# ripples_v40.net
KiCad netlist of a schematic drawn in EAGLE
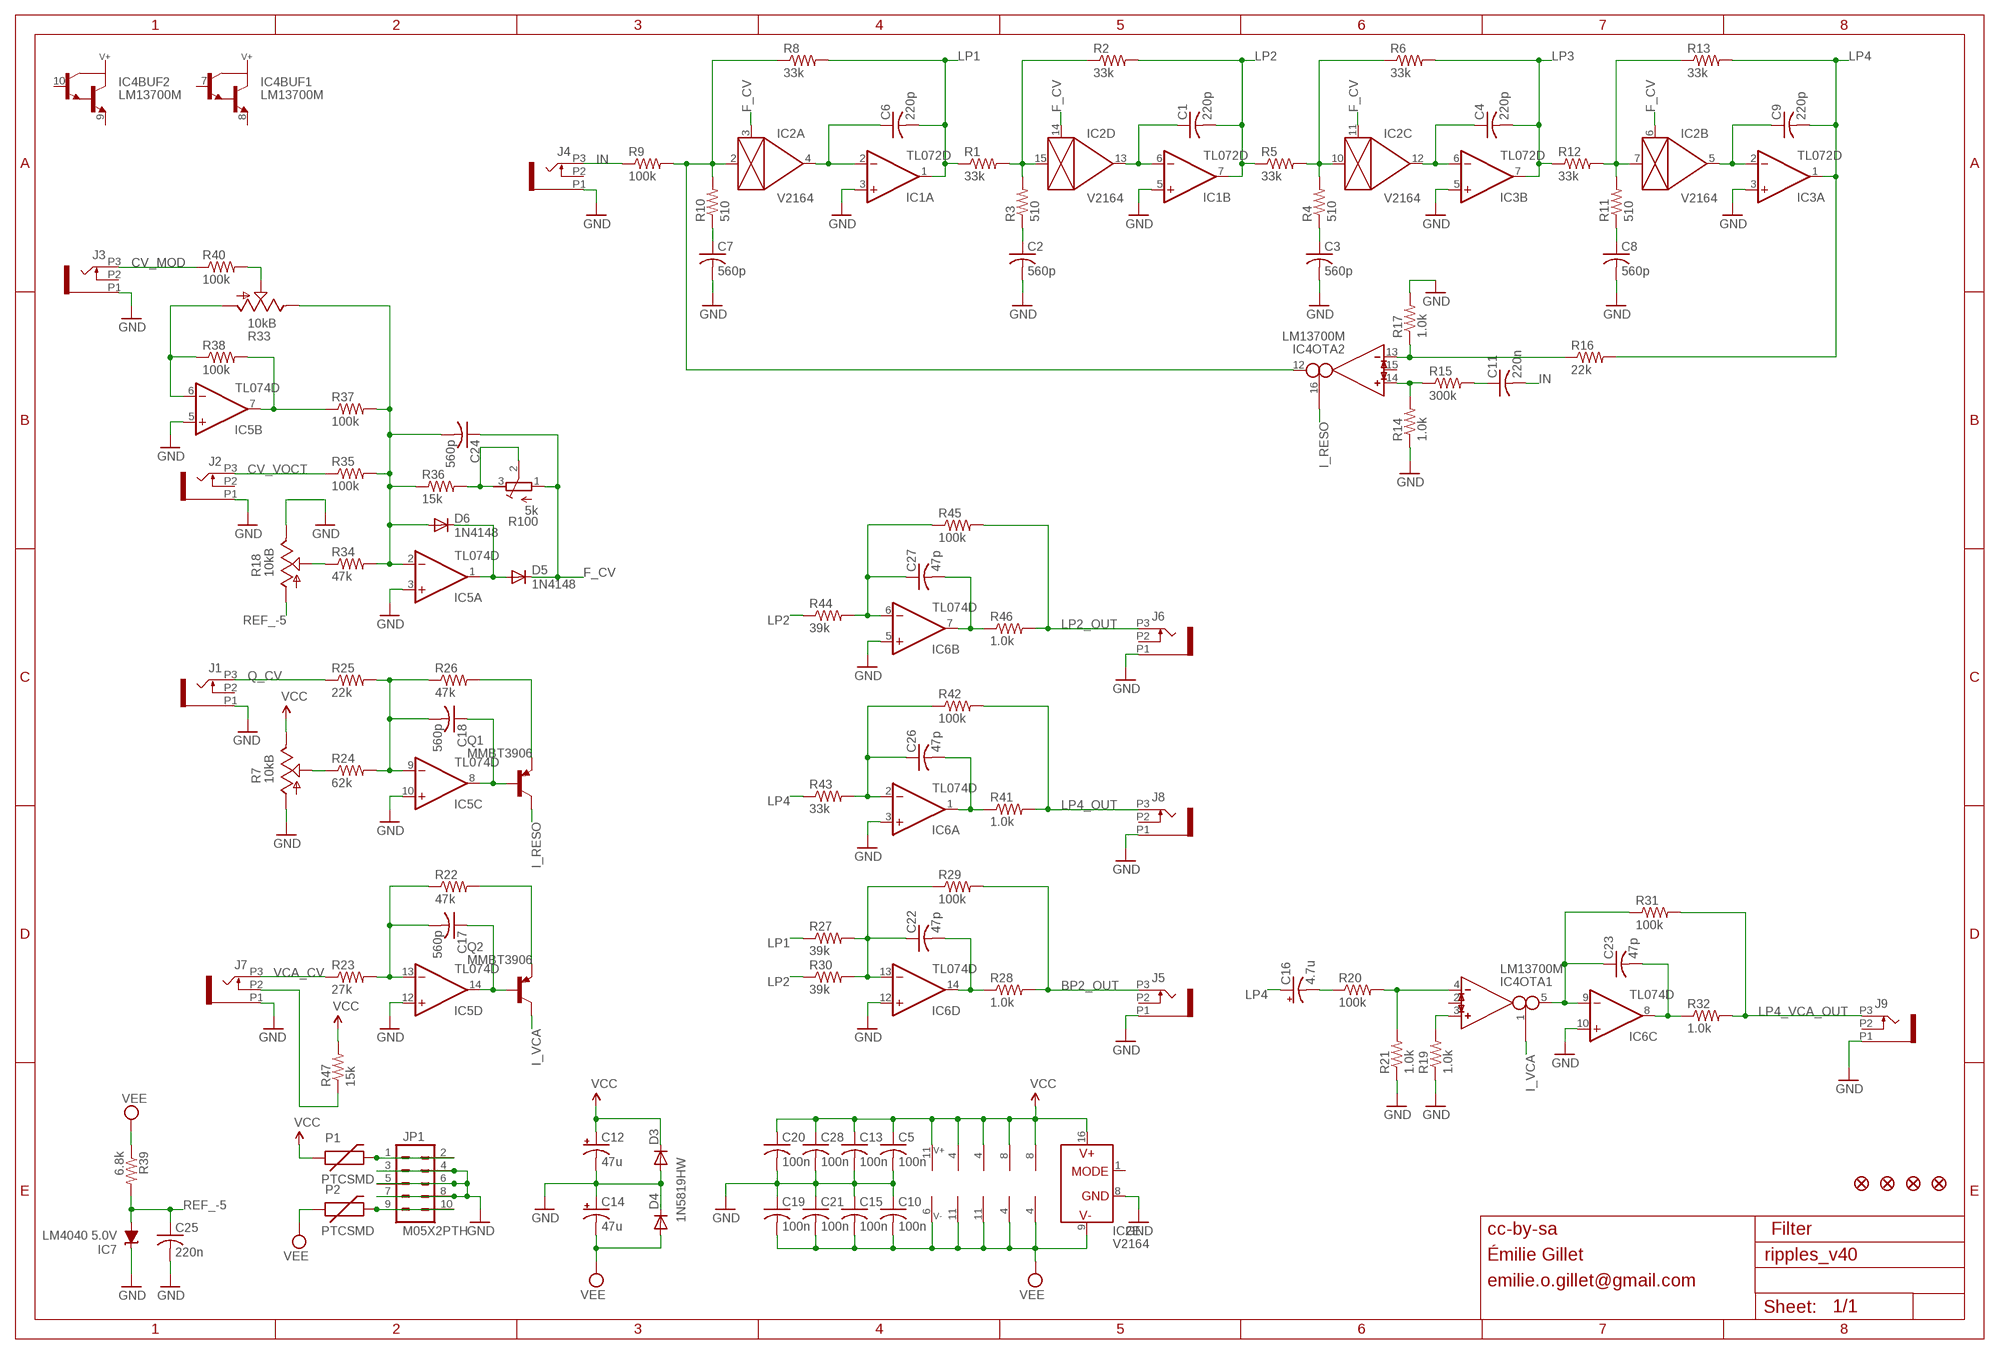
[diagram p0: schematic, sheet 1]

(export (version "E")
  (design (tool "Eeschema 10.0.6"))
  (components
    (comp (ref "C1")
      (value "220p")
      (footprint "eagle-import:C0603")
      (libsource (lib "eagle-import") (part "C-USC0603"))
    )
    (comp (ref "C2")
      (value "560p")
      (footprint "eagle-import:C0603")
      (libsource (lib "eagle-import") (part "C-USC0603"))
    )
    (comp (ref "C3")
      (value "560p")
      (footprint "eagle-import:C0603")
      (libsource (lib "eagle-import") (part "C-USC0603"))
    )
    (comp (ref "C4")
      (value "220p")
      (footprint "eagle-import:C0603")
      (libsource (lib "eagle-import") (part "C-USC0603"))
    )
    (comp (ref "C5")
      (value "100n")
      (footprint "eagle-import:C0603")
      (libsource (lib "eagle-import") (part "C-USC0603"))
    )
    (comp (ref "C6")
      (value "220p")
      (footprint "eagle-import:C0603")
      (libsource (lib "eagle-import") (part "C-USC0603"))
    )
    (comp (ref "C7")
      (value "560p")
      (footprint "eagle-import:C0603")
      (libsource (lib "eagle-import") (part "C-USC0603"))
    )
    (comp (ref "C8")
      (value "560p")
      (footprint "eagle-import:C0603")
      (libsource (lib "eagle-import") (part "C-USC0603"))
    )
    (comp (ref "C9")
      (value "220p")
      (footprint "eagle-import:C0603")
      (libsource (lib "eagle-import") (part "C-USC0603"))
    )
    (comp (ref "C10")
      (value "100n")
      (footprint "eagle-import:C0603")
      (libsource (lib "eagle-import") (part "C-USC0603"))
    )
    (comp (ref "C11")
      (value "220n")
      (footprint "eagle-import:C0603")
      (libsource (lib "eagle-import") (part "C-USC0603"))
    )
    (comp (ref "C12")
      (value "47u")
      (footprint "eagle-import:PANASONIC_D")
      (libsource (lib "eagle-import") (part "CPOL-USD"))
    )
    (comp (ref "C13")
      (value "100n")
      (footprint "eagle-import:C0603")
      (libsource (lib "eagle-import") (part "C-USC0603"))
    )
    (comp (ref "C14")
      (value "47u")
      (footprint "eagle-import:PANASONIC_D")
      (libsource (lib "eagle-import") (part "CPOL-USD"))
    )
    (comp (ref "C15")
      (value "100n")
      (footprint "eagle-import:C0603")
      (libsource (lib "eagle-import") (part "C-USC0603"))
    )
    (comp (ref "C16")
      (value "4.7u")
      (footprint "eagle-import:PANASONIC_B")
      (libsource (lib "eagle-import") (part "CPOL-USB"))
    )
    (comp (ref "C17")
      (value "560p")
      (footprint "eagle-import:C0603")
      (libsource (lib "eagle-import") (part "C-USC0603"))
    )
    (comp (ref "C18")
      (value "560p")
      (footprint "eagle-import:C0603")
      (libsource (lib "eagle-import") (part "C-USC0603"))
    )
    (comp (ref "C19")
      (value "100n")
      (footprint "eagle-import:C0603")
      (libsource (lib "eagle-import") (part "C-USC0603"))
    )
    (comp (ref "C20")
      (value "100n")
      (footprint "eagle-import:C0603")
      (libsource (lib "eagle-import") (part "C-USC0603"))
    )
    (comp (ref "C21")
      (value "100n")
      (footprint "eagle-import:C0603")
      (libsource (lib "eagle-import") (part "C-USC0603"))
    )
    (comp (ref "C22")
      (value "47p")
      (footprint "eagle-import:C0603")
      (libsource (lib "eagle-import") (part "C-USC0603"))
    )
    (comp (ref "C23")
      (value "47p")
      (footprint "eagle-import:C0603")
      (libsource (lib "eagle-import") (part "C-USC0603"))
    )
    (comp (ref "C24")
      (value "560p")
      (footprint "eagle-import:C0603")
      (libsource (lib "eagle-import") (part "C-USC0603"))
    )
    (comp (ref "C25")
      (value "220n")
      (footprint "eagle-import:C0603")
      (libsource (lib "eagle-import") (part "C-USC0603"))
    )
    (comp (ref "C26")
      (value "47p")
      (footprint "eagle-import:C0603")
      (libsource (lib "eagle-import") (part "C-USC0603"))
    )
    (comp (ref "C27")
      (value "47p")
      (footprint "eagle-import:C0603")
      (libsource (lib "eagle-import") (part "C-USC0603"))
    )
    (comp (ref "C28")
      (value "100n")
      (footprint "eagle-import:C0603")
      (libsource (lib "eagle-import") (part "C-USC0603"))
    )
    (comp (ref "D3")
      (value "1N5819HW")
      (footprint "eagle-import:SOD123")
      (libsource (lib "eagle-import") (part "DIODE-SOD123"))
    )
    (comp (ref "D4")
      (value "1N5819HW")
      (footprint "eagle-import:SOD123")
      (libsource (lib "eagle-import") (part "DIODE-SOD123"))
    )
    (comp (ref "D5")
      (value "1N4148")
      (footprint "eagle-import:SOD323-W")
      (libsource (lib "eagle-import") (part "DIODE-SOD323-W"))
    )
    (comp (ref "D6")
      (value "1N4148")
      (footprint "eagle-import:SOD323-W")
      (libsource (lib "eagle-import") (part "DIODE-SOD323-W"))
    )
    (comp (ref "F1")
      (value "FIDUCIAL1X2")
      (footprint "eagle-import:FIDUCIAL-1X2")
      (libsource (lib "eagle-import") (part "FIDUCIAL1X2"))
    )
    (comp (ref "F2")
      (value "FIDUCIAL1X2")
      (footprint "eagle-import:FIDUCIAL-1X2")
      (libsource (lib "eagle-import") (part "FIDUCIAL1X2"))
    )
    (comp (ref "F3")
      (value "FIDUCIAL1X2")
      (footprint "eagle-import:FIDUCIAL-1X2")
      (libsource (lib "eagle-import") (part "FIDUCIAL1X2"))
    )
    (comp (ref "F4")
      (value "FIDUCIAL1X2")
      (footprint "eagle-import:FIDUCIAL-1X2")
      (libsource (lib "eagle-import") (part "FIDUCIAL1X2"))
    )
    (comp (ref "IC1")
      (value "TL072D")
      (footprint "eagle-import:SO08")
      (libsource (lib "eagle-import") (part "TL072D"))
    )
    (comp (ref "IC2")
      (value "V2164")
      (footprint "eagle-import:SOIC16N")
      (libsource (lib "eagle-import") (part "SSM2164S"))
    )
    (comp (ref "IC3")
      (value "TL072D")
      (footprint "eagle-import:SO08")
      (libsource (lib "eagle-import") (part "TL072D"))
    )
    (comp (ref "IC4")
      (value "LM13700M")
      (footprint "eagle-import:SO16")
      (libsource (lib "eagle-import") (part "LM13700M"))
    )
    (comp (ref "IC5")
      (value "TL074D")
      (footprint "eagle-import:SO14")
      (libsource (lib "eagle-import") (part "TL074D"))
    )
    (comp (ref "IC6")
      (value "TL074D")
      (footprint "eagle-import:SO14")
      (libsource (lib "eagle-import") (part "TL074D"))
    )
    (comp (ref "IC7")
      (value "LM4040 5.0V")
      (footprint "eagle-import:DBZ_R-PDSO-G3")
      (libsource (lib "eagle-import") (part "LM4041DBZC12"))
    )
    (comp (ref "J1")
      (value "PJ301_THONKICONN6")
      (footprint "eagle-import:WQP_PJ_301M6")
      (libsource (lib "eagle-import") (part "PJ301_THONKICONN6"))
    )
    (comp (ref "J2")
      (value "PJ301_THONKICONN6")
      (footprint "eagle-import:WQP_PJ_301M6")
      (libsource (lib "eagle-import") (part "PJ301_THONKICONN6"))
    )
    (comp (ref "J3")
      (value "PJ301_THONKICONN6")
      (footprint "eagle-import:WQP_PJ_301M6")
      (libsource (lib "eagle-import") (part "PJ301_THONKICONN6"))
    )
    (comp (ref "J4")
      (value "PJ301_THONKICONN6")
      (footprint "eagle-import:WQP_PJ_301M6")
      (libsource (lib "eagle-import") (part "PJ301_THONKICONN6"))
    )
    (comp (ref "J5")
      (value "PJ301_THONKICONN6")
      (footprint "eagle-import:WQP_PJ_301M6")
      (libsource (lib "eagle-import") (part "PJ301_THONKICONN6"))
    )
    (comp (ref "J6")
      (value "PJ301_THONKICONN6")
      (footprint "eagle-import:WQP_PJ_301M6")
      (libsource (lib "eagle-import") (part "PJ301_THONKICONN6"))
    )
    (comp (ref "J7")
      (value "PJ301_THONKICONN6")
      (footprint "eagle-import:WQP_PJ_301M6")
      (libsource (lib "eagle-import") (part "PJ301_THONKICONN6"))
    )
    (comp (ref "J8")
      (value "PJ301_THONKICONN6")
      (footprint "eagle-import:WQP_PJ_301M6")
      (libsource (lib "eagle-import") (part "PJ301_THONKICONN6"))
    )
    (comp (ref "J9")
      (value "PJ301_THONKICONN6")
      (footprint "eagle-import:WQP_PJ_301M6")
      (libsource (lib "eagle-import") (part "PJ301_THONKICONN6"))
    )
    (comp (ref "JP1")
      (value "M05X2PTH")
      (footprint "eagle-import:AVR_ICSP")
      (libsource (lib "eagle-import") (part "M05X2PTH"))
    )
    (comp (ref "P1")
      (value "PTCSMD")
      (footprint "eagle-import:PTC-1206")
      (libsource (lib "eagle-import") (part "PTCSMD"))
    )
    (comp (ref "P2")
      (value "PTCSMD")
      (footprint "eagle-import:PTC-1206")
      (libsource (lib "eagle-import") (part "PTCSMD"))
    )
    (comp (ref "Q1")
      (value "MMBT3906")
      (footprint "eagle-import:SOT23-BEC")
      (libsource (lib "eagle-import") (part "-PNP-SOT23-BECMMBT3906LT1"))
    )
    (comp (ref "Q2")
      (value "MMBT3906")
      (footprint "eagle-import:SOT23-BEC")
      (libsource (lib "eagle-import") (part "-PNP-SOT23-BECMMBT3906LT1"))
    )
    (comp (ref "R1")
      (value "33k")
      (footprint "eagle-import:R0603")
      (libsource (lib "eagle-import") (part "R-US_R0603"))
    )
    (comp (ref "R2")
      (value "33k")
      (footprint "eagle-import:R0603")
      (libsource (lib "eagle-import") (part "R-US_R0603"))
    )
    (comp (ref "R3")
      (value "510")
      (footprint "eagle-import:R0603")
      (libsource (lib "eagle-import") (part "R-US_R0603"))
    )
    (comp (ref "R4")
      (value "510")
      (footprint "eagle-import:R0603")
      (libsource (lib "eagle-import") (part "R-US_R0603"))
    )
    (comp (ref "R5")
      (value "33k")
      (footprint "eagle-import:R0603")
      (libsource (lib "eagle-import") (part "R-US_R0603"))
    )
    (comp (ref "R6")
      (value "33k")
      (footprint "eagle-import:R0603")
      (libsource (lib "eagle-import") (part "R-US_R0603"))
    )
    (comp (ref "R7")
      (value "10kB")
      (footprint "eagle-import:ALPS_POT_VERTICAL_PS")
      (libsource (lib "eagle-import") (part "POT_USVERTICAL_PS"))
    )
    (comp (ref "R8")
      (value "33k")
      (footprint "eagle-import:R0603")
      (libsource (lib "eagle-import") (part "R-US_R0603"))
    )
    (comp (ref "R9")
      (value "100k")
      (footprint "eagle-import:R0603")
      (libsource (lib "eagle-import") (part "R-US_R0603"))
    )
    (comp (ref "R10")
      (value "510")
      (footprint "eagle-import:R0603")
      (libsource (lib "eagle-import") (part "R-US_R0603"))
    )
    (comp (ref "R11")
      (value "510")
      (footprint "eagle-import:R0603")
      (libsource (lib "eagle-import") (part "R-US_R0603"))
    )
    (comp (ref "R12")
      (value "33k")
      (footprint "eagle-import:R0603")
      (libsource (lib "eagle-import") (part "R-US_R0603"))
    )
    (comp (ref "R13")
      (value "33k")
      (footprint "eagle-import:R0603")
      (libsource (lib "eagle-import") (part "R-US_R0603"))
    )
    (comp (ref "R14")
      (value "1.0k")
      (footprint "eagle-import:R0603")
      (libsource (lib "eagle-import") (part "R-US_R0603"))
    )
    (comp (ref "R15")
      (value "300k")
      (footprint "eagle-import:R0603")
      (libsource (lib "eagle-import") (part "R-US_R0603"))
    )
    (comp (ref "R16")
      (value "22k")
      (footprint "eagle-import:R0603")
      (libsource (lib "eagle-import") (part "R-US_R0603"))
    )
    (comp (ref "R17")
      (value "1.0k")
      (footprint "eagle-import:R0603")
      (libsource (lib "eagle-import") (part "R-US_R0603"))
    )
    (comp (ref "R18")
      (value "10kB")
      (footprint "eagle-import:ALPS_POT_VERTICAL_PS")
      (libsource (lib "eagle-import") (part "POT_USVERTICAL_PS"))
    )
    (comp (ref "R19")
      (value "1.0k")
      (footprint "eagle-import:R0603")
      (libsource (lib "eagle-import") (part "R-US_R0603"))
    )
    (comp (ref "R20")
      (value "100k")
      (footprint "eagle-import:R0603")
      (libsource (lib "eagle-import") (part "R-US_R0603"))
    )
    (comp (ref "R21")
      (value "1.0k")
      (footprint "eagle-import:R0603")
      (libsource (lib "eagle-import") (part "R-US_R0603"))
    )
    (comp (ref "R22")
      (value "47k")
      (footprint "eagle-import:R0603")
      (libsource (lib "eagle-import") (part "R-US_R0603"))
    )
    (comp (ref "R23")
      (value "27k")
      (footprint "eagle-import:R0603")
      (libsource (lib "eagle-import") (part "R-US_R0603"))
    )
    (comp (ref "R24")
      (value "62k")
      (footprint "eagle-import:R0603")
      (libsource (lib "eagle-import") (part "R-US_R0603"))
    )
    (comp (ref "R25")
      (value "22k")
      (footprint "eagle-import:R0603")
      (libsource (lib "eagle-import") (part "R-US_R0603"))
    )
    (comp (ref "R26")
      (value "47k")
      (footprint "eagle-import:R0603")
      (libsource (lib "eagle-import") (part "R-US_R0603"))
    )
    (comp (ref "R27")
      (value "39k")
      (footprint "eagle-import:R0603")
      (libsource (lib "eagle-import") (part "R-US_R0603"))
    )
    (comp (ref "R28")
      (value "1.0k")
      (footprint "eagle-import:R0603")
      (libsource (lib "eagle-import") (part "R-US_R0603"))
    )
    (comp (ref "R29")
      (value "100k")
      (footprint "eagle-import:R0603")
      (libsource (lib "eagle-import") (part "R-US_R0603"))
    )
    (comp (ref "R30")
      (value "39k")
      (footprint "eagle-import:R0603")
      (libsource (lib "eagle-import") (part "R-US_R0603"))
    )
    (comp (ref "R31")
      (value "100k")
      (footprint "eagle-import:R0603")
      (libsource (lib "eagle-import") (part "R-US_R0603"))
    )
    (comp (ref "R32")
      (value "1.0k")
      (footprint "eagle-import:R0603")
      (libsource (lib "eagle-import") (part "R-US_R0603"))
    )
    (comp (ref "R33")
      (value "10kB")
      (footprint "eagle-import:ALPS_POT_VERTICAL_PS")
      (libsource (lib "eagle-import") (part "POT_USVERTICAL_PS"))
    )
    (comp (ref "R34")
      (value "47k")
      (footprint "eagle-import:R0603")
      (libsource (lib "eagle-import") (part "R-US_R0603"))
    )
    (comp (ref "R35")
      (value "100k")
      (footprint "eagle-import:R0603")
      (libsource (lib "eagle-import") (part "R-US_R0603"))
    )
    (comp (ref "R36")
      (value "15k")
      (footprint "eagle-import:R0603")
      (libsource (lib "eagle-import") (part "R-US_R0603"))
    )
    (comp (ref "R37")
      (value "100k")
      (footprint "eagle-import:R0603")
      (libsource (lib "eagle-import") (part "R-US_R0603"))
    )
    (comp (ref "R38")
      (value "100k")
      (footprint "eagle-import:R0603")
      (libsource (lib "eagle-import") (part "R-US_R0603"))
    )
    (comp (ref "R39")
      (value "6.8k")
      (footprint "eagle-import:R0603")
      (libsource (lib "eagle-import") (part "resistor_R-US_R0603"))
    )
    (comp (ref "R40")
      (value "100k")
      (footprint "eagle-import:R0603")
      (libsource (lib "eagle-import") (part "R-US_R0603"))
    )
    (comp (ref "R41")
      (value "1.0k")
      (footprint "eagle-import:R0603")
      (libsource (lib "eagle-import") (part "R-US_R0603"))
    )
    (comp (ref "R42")
      (value "100k")
      (footprint "eagle-import:R0603")
      (libsource (lib "eagle-import") (part "R-US_R0603"))
    )
    (comp (ref "R43")
      (value "33k")
      (footprint "eagle-import:R0603")
      (libsource (lib "eagle-import") (part "R-US_R0603"))
    )
    (comp (ref "R44")
      (value "39k")
      (footprint "eagle-import:R0603")
      (libsource (lib "eagle-import") (part "R-US_R0603"))
    )
    (comp (ref "R45")
      (value "100k")
      (footprint "eagle-import:R0603")
      (libsource (lib "eagle-import") (part "R-US_R0603"))
    )
    (comp (ref "R46")
      (value "1.0k")
      (footprint "eagle-import:R0603")
      (libsource (lib "eagle-import") (part "R-US_R0603"))
    )
    (comp (ref "R47")
      (value "15k")
      (footprint "eagle-import:R0603")
      (libsource (lib "eagle-import") (part "R-US_R0603"))
    )
    (comp (ref "R100")
      (value "5k")
      (footprint "eagle-import:RTRIM3296X")
      (libsource (lib "eagle-import") (part "R-TRIMM3296X"))
    )
  )
  (nets
    (net (code "1") (name "/BP2_OUT") (class "Default")
      (node (ref "J5") (pin "P3") (pinfunction "3_P3") (pintype "passive"))
      (node (ref "R28") (pin "2") (pinfunction "2_2") (pintype "passive"))
      (node (ref "R29") (pin "2") (pinfunction "2_2") (pintype "passive"))
    )
    (net (code "2") (name "/CV_MOD") (class "Default")
      (node (ref "J3") (pin "P3") (pinfunction "3_P3") (pintype "passive"))
      (node (ref "R40") (pin "1") (pinfunction "1_1") (pintype "passive"))
    )
    (net (code "3") (name "/CV_VOCT") (class "Default")
      (node (ref "J2") (pin "P3") (pinfunction "3_P3") (pintype "passive"))
      (node (ref "R35") (pin "1") (pinfunction "1_1") (pintype "passive"))
    )
    (net (code "4") (name "/F_CV") (class "Default")
      (node (ref "C24") (pin "1") (pinfunction "1_1") (pintype "passive"))
      (node (ref "D5") (pin "C") (pinfunction "C_C") (pintype "passive"))
      (node (ref "IC2") (pin "11") (pinfunction "CTRL_11") (pintype "input"))
      (node (ref "IC2") (pin "14") (pinfunction "CTRL_14") (pintype "input"))
      (node (ref "IC2") (pin "3") (pinfunction "CTRL_3") (pintype "input"))
      (node (ref "IC2") (pin "6") (pinfunction "CTRL_6") (pintype "input"))
      (node (ref "R100") (pin "1") (pinfunction "E_1") (pintype "passive"))
    )
    (net (code "5") (name "/IN") (class "Default")
      (node (ref "C11") (pin "2") (pinfunction "2_2") (pintype "passive"))
      (node (ref "J4") (pin "P3") (pinfunction "3_P3") (pintype "passive"))
      (node (ref "R9") (pin "1") (pinfunction "1_1") (pintype "passive"))
    )
    (net (code "6") (name "/I_RESO") (class "Default")
      (node (ref "IC4") (pin "16") (pinfunction "I_BIAS_16") (pintype "input"))
      (node (ref "Q1") (pin "C") (pinfunction "C_C") (pintype "passive"))
    )
    (net (code "7") (name "/I_VCA") (class "Default")
      (node (ref "IC4") (pin "1") (pinfunction "I_BIAS_1") (pintype "input"))
      (node (ref "Q2") (pin "C") (pinfunction "C_C") (pintype "passive"))
    )
    (net (code "8") (name "/LP1") (class "Default")
      (node (ref "C6") (pin "2") (pinfunction "2_2") (pintype "passive"))
      (node (ref "IC1") (pin "1") (pinfunction "OUT_1") (pintype "output"))
      (node (ref "R1") (pin "1") (pinfunction "1_1") (pintype "passive"))
      (node (ref "R27") (pin "1") (pinfunction "1_1") (pintype "passive"))
      (node (ref "R8") (pin "2") (pinfunction "2_2") (pintype "passive"))
    )
    (net (code "9") (name "/LP2") (class "Default")
      (node (ref "C1") (pin "2") (pinfunction "2_2") (pintype "passive"))
      (node (ref "IC1") (pin "7") (pinfunction "OUT_7") (pintype "output"))
      (node (ref "R2") (pin "2") (pinfunction "2_2") (pintype "passive"))
      (node (ref "R30") (pin "1") (pinfunction "1_1") (pintype "passive"))
      (node (ref "R44") (pin "1") (pinfunction "1_1") (pintype "passive"))
      (node (ref "R5") (pin "1") (pinfunction "1_1") (pintype "passive"))
    )
    (net (code "10") (name "/LP2_OUT") (class "Default")
      (node (ref "J6") (pin "P3") (pinfunction "3_P3") (pintype "passive"))
      (node (ref "R45") (pin "2") (pinfunction "2_2") (pintype "passive"))
      (node (ref "R46") (pin "2") (pinfunction "2_2") (pintype "passive"))
    )
    (net (code "11") (name "/LP3") (class "Default")
      (node (ref "C4") (pin "2") (pinfunction "2_2") (pintype "passive"))
      (node (ref "IC3") (pin "7") (pinfunction "OUT_7") (pintype "output"))
      (node (ref "R12") (pin "1") (pinfunction "1_1") (pintype "passive"))
      (node (ref "R6") (pin "2") (pinfunction "2_2") (pintype "passive"))
    )
    (net (code "12") (name "/LP4") (class "Default")
      (node (ref "C16") (pin "+") (pinfunction "+_+") (pintype "passive"))
      (node (ref "C9") (pin "2") (pinfunction "2_2") (pintype "passive"))
      (node (ref "IC3") (pin "1") (pinfunction "OUT_1") (pintype "output"))
      (node (ref "R13") (pin "2") (pinfunction "2_2") (pintype "passive"))
      (node (ref "R16") (pin "2") (pinfunction "2_2") (pintype "passive"))
      (node (ref "R43") (pin "1") (pinfunction "1_1") (pintype "passive"))
    )
    (net (code "13") (name "/LP4_OUT") (class "Default")
      (node (ref "J8") (pin "P3") (pinfunction "3_P3") (pintype "passive"))
      (node (ref "R41") (pin "2") (pinfunction "2_2") (pintype "passive"))
      (node (ref "R42") (pin "2") (pinfunction "2_2") (pintype "passive"))
    )
    (net (code "14") (name "/LP4_VCA_OUT") (class "Default")
      (node (ref "J9") (pin "P3") (pinfunction "3_P3") (pintype "passive"))
      (node (ref "R31") (pin "2") (pinfunction "2_2") (pintype "passive"))
      (node (ref "R32") (pin "2") (pinfunction "2_2") (pintype "passive"))
    )
    (net (code "15") (name "/Q_CV") (class "Default")
      (node (ref "J1") (pin "P3") (pinfunction "3_P3") (pintype "passive"))
      (node (ref "R25") (pin "1") (pinfunction "1_1") (pintype "passive"))
    )
    (net (code "16") (name "/REF_-5") (class "Default")
      (node (ref "C25") (pin "1") (pinfunction "1_1") (pintype "passive"))
      (node (ref "IC7") (pin "2") (pinfunction "A_2") (pintype "passive"))
      (node (ref "R18") (pin "P$3") (pinfunction "A_P$3") (pintype "passive"))
      (node (ref "R39") (pin "2") (pinfunction "2_2") (pintype "passive"))
    )
    (net (code "17") (name "/VCA_CV") (class "Default")
      (node (ref "J7") (pin "P3") (pinfunction "3_P3") (pintype "passive"))
      (node (ref "R23") (pin "1") (pinfunction "1_1") (pintype "passive"))
    )
    (net (code "18") (name "GND") (class "Default")
      (node (ref "C10") (pin "1") (pinfunction "1_1") (pintype "passive"))
      (node (ref "C12") (pin "-") (pinfunction "-_-") (pintype "passive"))
      (node (ref "C13") (pin "2") (pinfunction "2_2") (pintype "passive"))
      (node (ref "C14") (pin "+") (pinfunction "+_+") (pintype "passive"))
      (node (ref "C15") (pin "1") (pinfunction "1_1") (pintype "passive"))
      (node (ref "C19") (pin "1") (pinfunction "1_1") (pintype "passive"))
      (node (ref "C2") (pin "2") (pinfunction "2_2") (pintype "passive"))
      (node (ref "C20") (pin "2") (pinfunction "2_2") (pintype "passive"))
      (node (ref "C21") (pin "1") (pinfunction "1_1") (pintype "passive"))
      (node (ref "C25") (pin "2") (pinfunction "2_2") (pintype "passive"))
      (node (ref "C28") (pin "2") (pinfunction "2_2") (pintype "passive"))
      (node (ref "C3") (pin "2") (pinfunction "2_2") (pintype "passive"))
      (node (ref "C5") (pin "2") (pinfunction "2_2") (pintype "passive"))
      (node (ref "C7") (pin "2") (pinfunction "2_2") (pintype "passive"))
      (node (ref "C8") (pin "2") (pinfunction "2_2") (pintype "passive"))
      (node (ref "D3") (pin "A") (pinfunction "A_A") (pintype "passive"))
      (node (ref "D4") (pin "C") (pinfunction "C_C") (pintype "passive"))
      (node (ref "IC1") (pin "3") (pinfunction "+IN_3") (pintype "input"))
      (node (ref "IC1") (pin "5") (pinfunction "+IN_5") (pintype "input"))
      (node (ref "IC2") (pin "8") (pinfunction "GND_8") (pintype "power_in"))
      (node (ref "IC3") (pin "3") (pinfunction "+IN_3") (pintype "input"))
      (node (ref "IC3") (pin "5") (pinfunction "+IN_5") (pintype "input"))
      (node (ref "IC5") (pin "10") (pinfunction "+IN_10") (pintype "input"))
      (node (ref "IC5") (pin "12") (pinfunction "+IN_12") (pintype "input"))
      (node (ref "IC5") (pin "3") (pinfunction "+IN_3") (pintype "input"))
      (node (ref "IC5") (pin "5") (pinfunction "+IN_5") (pintype "input"))
      (node (ref "IC6") (pin "10") (pinfunction "+IN_10") (pintype "input"))
      (node (ref "IC6") (pin "12") (pinfunction "+IN_12") (pintype "input"))
      (node (ref "IC6") (pin "3") (pinfunction "+IN_3") (pintype "input"))
      (node (ref "IC6") (pin "5") (pinfunction "+IN_5") (pintype "input"))
      (node (ref "IC7") (pin "1") (pinfunction "C_1") (pintype "passive"))
      (node (ref "J1") (pin "P1") (pinfunction "1_P1") (pintype "passive"))
      (node (ref "J2") (pin "P1") (pinfunction "1_P1") (pintype "passive"))
      (node (ref "J3") (pin "P1") (pinfunction "1_P1") (pintype "passive"))
      (node (ref "J4") (pin "P1") (pinfunction "1_P1") (pintype "passive"))
      (node (ref "J5") (pin "P1") (pinfunction "1_P1") (pintype "passive"))
      (node (ref "J6") (pin "P1") (pinfunction "1_P1") (pintype "passive"))
      (node (ref "J7") (pin "P1") (pinfunction "1_P1") (pintype "passive"))
      (node (ref "J8") (pin "P1") (pinfunction "1_P1") (pintype "passive"))
      (node (ref "J9") (pin "P1") (pinfunction "1_P1") (pintype "passive"))
      (node (ref "JP1") (pin "3") (pinfunction "3_3") (pintype "passive"))
      (node (ref "JP1") (pin "4") (pinfunction "4_4") (pintype "passive"))
      (node (ref "JP1") (pin "5") (pinfunction "5_5") (pintype "passive"))
      (node (ref "JP1") (pin "6") (pinfunction "6_6") (pintype "passive"))
      (node (ref "JP1") (pin "7") (pinfunction "7_7") (pintype "passive"))
      (node (ref "JP1") (pin "8") (pinfunction "8_8") (pintype "passive"))
      (node (ref "R14") (pin "1") (pinfunction "1_1") (pintype "passive"))
      (node (ref "R17") (pin "2") (pinfunction "2_2") (pintype "passive"))
      (node (ref "R18") (pin "P$1") (pinfunction "E_P$1") (pintype "passive"))
      (node (ref "R19") (pin "1") (pinfunction "1_1") (pintype "passive"))
      (node (ref "R21") (pin "1") (pinfunction "1_1") (pintype "passive"))
      (node (ref "R7") (pin "P$3") (pinfunction "A_P$3") (pintype "passive"))
    )
    (net (code "19") (name "Net-(C2-Pad1)") (class "Default")
      (node (ref "C2") (pin "1") (pinfunction "1_1") (pintype "passive"))
      (node (ref "R3") (pin "1") (pinfunction "1_1") (pintype "passive"))
    )
    (net (code "20") (name "Net-(C3-Pad1)") (class "Default")
      (node (ref "C3") (pin "1") (pinfunction "1_1") (pintype "passive"))
      (node (ref "R4") (pin "1") (pinfunction "1_1") (pintype "passive"))
    )
    (net (code "21") (name "Net-(C7-Pad1)") (class "Default")
      (node (ref "C7") (pin "1") (pinfunction "1_1") (pintype "passive"))
      (node (ref "R10") (pin "1") (pinfunction "1_1") (pintype "passive"))
    )
    (net (code "22") (name "Net-(C8-Pad1)") (class "Default")
      (node (ref "C8") (pin "1") (pinfunction "1_1") (pintype "passive"))
      (node (ref "R11") (pin "1") (pinfunction "1_1") (pintype "passive"))
    )
    (net (code "23") (name "Net-(C11-Pad1)") (class "Default")
      (node (ref "C11") (pin "1") (pinfunction "1_1") (pintype "passive"))
      (node (ref "R15") (pin "2") (pinfunction "2_2") (pintype "passive"))
    )
    (net (code "24") (name "Net-(C16-Pad-)") (class "Default")
      (node (ref "C16") (pin "-") (pinfunction "-_-") (pintype "passive"))
      (node (ref "R20") (pin "1") (pinfunction "1_1") (pintype "passive"))
    )
    (net (code "25") (name "Net-(IC1A--IN)") (class "Default")
      (node (ref "C6") (pin "1") (pinfunction "1_1") (pintype "passive"))
      (node (ref "IC1") (pin "2") (pinfunction "-IN_2") (pintype "input"))
      (node (ref "IC2") (pin "4") (pinfunction "OUT_4") (pintype "output"))
    )
    (net (code "26") (name "Net-(IC1B--IN)") (class "Default")
      (node (ref "C1") (pin "1") (pinfunction "1_1") (pintype "passive"))
      (node (ref "IC1") (pin "6") (pinfunction "-IN_6") (pintype "input"))
      (node (ref "IC2") (pin "13") (pinfunction "OUT_13") (pintype "output"))
    )
    (net (code "27") (name "Net-(IC2A-IN)") (class "Default")
      (node (ref "IC2") (pin "2") (pinfunction "IN_2") (pintype "input"))
      (node (ref "IC4") (pin "12") (pinfunction "OUT_12") (pintype "output"))
      (node (ref "R10") (pin "2") (pinfunction "2_2") (pintype "passive"))
      (node (ref "R8") (pin "1") (pinfunction "1_1") (pintype "passive"))
      (node (ref "R9") (pin "2") (pinfunction "2_2") (pintype "passive"))
    )
    (net (code "28") (name "Net-(IC2B-IN)") (class "Default")
      (node (ref "IC2") (pin "7") (pinfunction "IN_7") (pintype "input"))
      (node (ref "R11") (pin "2") (pinfunction "2_2") (pintype "passive"))
      (node (ref "R12") (pin "2") (pinfunction "2_2") (pintype "passive"))
      (node (ref "R13") (pin "1") (pinfunction "1_1") (pintype "passive"))
    )
    (net (code "29") (name "Net-(IC2B-OUT)") (class "Default")
      (node (ref "C9") (pin "1") (pinfunction "1_1") (pintype "passive"))
      (node (ref "IC2") (pin "5") (pinfunction "OUT_5") (pintype "output"))
      (node (ref "IC3") (pin "2") (pinfunction "-IN_2") (pintype "input"))
    )
    (net (code "30") (name "Net-(IC2C-IN)") (class "Default")
      (node (ref "IC2") (pin "10") (pinfunction "IN_10") (pintype "input"))
      (node (ref "R4") (pin "2") (pinfunction "2_2") (pintype "passive"))
      (node (ref "R5") (pin "2") (pinfunction "2_2") (pintype "passive"))
      (node (ref "R6") (pin "1") (pinfunction "1_1") (pintype "passive"))
    )
    (net (code "31") (name "Net-(IC2C-OUT)") (class "Default")
      (node (ref "C4") (pin "1") (pinfunction "1_1") (pintype "passive"))
      (node (ref "IC2") (pin "12") (pinfunction "OUT_12") (pintype "output"))
      (node (ref "IC3") (pin "6") (pinfunction "-IN_6") (pintype "input"))
    )
    (net (code "32") (name "Net-(IC2D-IN)") (class "Default")
      (node (ref "IC2") (pin "15") (pinfunction "IN_15") (pintype "input"))
      (node (ref "R1") (pin "2") (pinfunction "2_2") (pintype "passive"))
      (node (ref "R2") (pin "1") (pinfunction "1_1") (pintype "passive"))
      (node (ref "R3") (pin "2") (pinfunction "2_2") (pintype "passive"))
    )
    (net (code "33") (name "Net-(IC4C-IN_N)") (class "Default")
      (node (ref "IC4") (pin "4") (pinfunction "IN_N_4") (pintype "input"))
      (node (ref "R20") (pin "2") (pinfunction "2_2") (pintype "passive"))
      (node (ref "R21") (pin "2") (pinfunction "2_2") (pintype "passive"))
    )
    (net (code "34") (name "Net-(IC4C-IN_P)") (class "Default")
      (node (ref "IC4") (pin "3") (pinfunction "IN_P_3") (pintype "input"))
      (node (ref "R19") (pin "2") (pinfunction "2_2") (pintype "passive"))
    )
    (net (code "35") (name "Net-(IC4C-OUT)") (class "Default")
      (node (ref "C23") (pin "1") (pinfunction "1_1") (pintype "passive"))
      (node (ref "IC4") (pin "5") (pinfunction "OUT_5") (pintype "output"))
      (node (ref "IC6") (pin "9") (pinfunction "-IN_9") (pintype "input"))
      (node (ref "R31") (pin "1") (pinfunction "1_1") (pintype "passive"))
    )
    (net (code "36") (name "Net-(IC4D-IN_N)") (class "Default")
      (node (ref "IC4") (pin "13") (pinfunction "IN_N_13") (pintype "input"))
      (node (ref "R16") (pin "1") (pinfunction "1_1") (pintype "passive"))
      (node (ref "R17") (pin "1") (pinfunction "1_1") (pintype "passive"))
    )
    (net (code "37") (name "Net-(IC4D-IN_P)") (class "Default")
      (node (ref "IC4") (pin "14") (pinfunction "IN_P_14") (pintype "input"))
      (node (ref "R14") (pin "2") (pinfunction "2_2") (pintype "passive"))
      (node (ref "R15") (pin "1") (pinfunction "1_1") (pintype "passive"))
    )
    (net (code "38") (name "Net-(IC5A--IN)") (class "Default")
      (node (ref "C24") (pin "2") (pinfunction "2_2") (pintype "passive"))
      (node (ref "D6") (pin "A") (pinfunction "A_A") (pintype "passive"))
      (node (ref "IC5") (pin "2") (pinfunction "-IN_2") (pintype "input"))
      (node (ref "R33") (pin "P$1") (pinfunction "E_P$1") (pintype "passive"))
      (node (ref "R34") (pin "2") (pinfunction "2_2") (pintype "passive"))
      (node (ref "R35") (pin "2") (pinfunction "2_2") (pintype "passive"))
      (node (ref "R36") (pin "1") (pinfunction "1_1") (pintype "passive"))
      (node (ref "R37") (pin "2") (pinfunction "2_2") (pintype "passive"))
    )
    (net (code "39") (name "Net-(IC5A-OUT)") (class "Default")
      (node (ref "D5") (pin "A") (pinfunction "A_A") (pintype "passive"))
      (node (ref "D6") (pin "C") (pinfunction "C_C") (pintype "passive"))
      (node (ref "IC5") (pin "1") (pinfunction "OUT_1") (pintype "output"))
    )
    (net (code "40") (name "Net-(IC5B--IN)") (class "Default")
      (node (ref "IC5") (pin "6") (pinfunction "-IN_6") (pintype "input"))
      (node (ref "R33") (pin "P$3") (pinfunction "A_P$3") (pintype "passive"))
      (node (ref "R38") (pin "1") (pinfunction "1_1") (pintype "passive"))
    )
    (net (code "41") (name "Net-(IC5B-OUT)") (class "Default")
      (node (ref "IC5") (pin "7") (pinfunction "OUT_7") (pintype "output"))
      (node (ref "R37") (pin "1") (pinfunction "1_1") (pintype "passive"))
      (node (ref "R38") (pin "2") (pinfunction "2_2") (pintype "passive"))
    )
    (net (code "42") (name "Net-(IC5C--IN)") (class "Default")
      (node (ref "C18") (pin "2") (pinfunction "2_2") (pintype "passive"))
      (node (ref "IC5") (pin "9") (pinfunction "-IN_9") (pintype "input"))
      (node (ref "R24") (pin "2") (pinfunction "2_2") (pintype "passive"))
      (node (ref "R25") (pin "2") (pinfunction "2_2") (pintype "passive"))
      (node (ref "R26") (pin "1") (pinfunction "1_1") (pintype "passive"))
    )
    (net (code "43") (name "Net-(IC5C-OUT)") (class "Default")
      (node (ref "C18") (pin "1") (pinfunction "1_1") (pintype "passive"))
      (node (ref "IC5") (pin "8") (pinfunction "OUT_8") (pintype "output"))
      (node (ref "Q1") (pin "B") (pinfunction "B_B") (pintype "passive"))
    )
    (net (code "44") (name "Net-(IC5D--IN)") (class "Default")
      (node (ref "C17") (pin "2") (pinfunction "2_2") (pintype "passive"))
      (node (ref "IC5") (pin "13") (pinfunction "-IN_13") (pintype "input"))
      (node (ref "R22") (pin "1") (pinfunction "1_1") (pintype "passive"))
      (node (ref "R23") (pin "2") (pinfunction "2_2") (pintype "passive"))
    )
    (net (code "45") (name "Net-(IC5D-OUT)") (class "Default")
      (node (ref "C17") (pin "1") (pinfunction "1_1") (pintype "passive"))
      (node (ref "IC5") (pin "14") (pinfunction "OUT_14") (pintype "output"))
      (node (ref "Q2") (pin "B") (pinfunction "B_B") (pintype "passive"))
    )
    (net (code "46") (name "Net-(IC6A--IN)") (class "Default")
      (node (ref "C26") (pin "1") (pinfunction "1_1") (pintype "passive"))
      (node (ref "IC6") (pin "2") (pinfunction "-IN_2") (pintype "input"))
      (node (ref "R42") (pin "1") (pinfunction "1_1") (pintype "passive"))
      (node (ref "R43") (pin "2") (pinfunction "2_2") (pintype "passive"))
    )
    (net (code "47") (name "Net-(IC6A-OUT)") (class "Default")
      (node (ref "C26") (pin "2") (pinfunction "2_2") (pintype "passive"))
      (node (ref "IC6") (pin "1") (pinfunction "OUT_1") (pintype "output"))
      (node (ref "R41") (pin "1") (pinfunction "1_1") (pintype "passive"))
    )
    (net (code "48") (name "Net-(IC6B--IN)") (class "Default")
      (node (ref "C27") (pin "1") (pinfunction "1_1") (pintype "passive"))
      (node (ref "IC6") (pin "6") (pinfunction "-IN_6") (pintype "input"))
      (node (ref "R44") (pin "2") (pinfunction "2_2") (pintype "passive"))
      (node (ref "R45") (pin "1") (pinfunction "1_1") (pintype "passive"))
    )
    (net (code "49") (name "Net-(IC6B-OUT)") (class "Default")
      (node (ref "C27") (pin "2") (pinfunction "2_2") (pintype "passive"))
      (node (ref "IC6") (pin "7") (pinfunction "OUT_7") (pintype "output"))
      (node (ref "R46") (pin "1") (pinfunction "1_1") (pintype "passive"))
    )
    (net (code "50") (name "Net-(IC6C-OUT)") (class "Default")
      (node (ref "C23") (pin "2") (pinfunction "2_2") (pintype "passive"))
      (node (ref "IC6") (pin "8") (pinfunction "OUT_8") (pintype "output"))
      (node (ref "R32") (pin "1") (pinfunction "1_1") (pintype "passive"))
    )
    (net (code "51") (name "Net-(IC6D--IN)") (class "Default")
      (node (ref "C22") (pin "1") (pinfunction "1_1") (pintype "passive"))
      (node (ref "IC6") (pin "13") (pinfunction "-IN_13") (pintype "input"))
      (node (ref "R27") (pin "2") (pinfunction "2_2") (pintype "passive"))
      (node (ref "R29") (pin "1") (pinfunction "1_1") (pintype "passive"))
      (node (ref "R30") (pin "2") (pinfunction "2_2") (pintype "passive"))
    )
    (net (code "52") (name "Net-(IC6D-OUT)") (class "Default")
      (node (ref "C22") (pin "2") (pinfunction "2_2") (pintype "passive"))
      (node (ref "IC6") (pin "14") (pinfunction "OUT_14") (pintype "output"))
      (node (ref "R28") (pin "1") (pinfunction "1_1") (pintype "passive"))
    )
    (net (code "53") (name "Net-(J7-2)") (class "Default")
      (node (ref "J7") (pin "P2") (pinfunction "2_P2") (pintype "passive"))
      (node (ref "R47") (pin "1") (pinfunction "1_1") (pintype "passive"))
    )
    (net (code "54") (name "Net-(JP1-Pad1)") (class "Default")
      (node (ref "JP1") (pin "1") (pinfunction "1_1") (pintype "passive"))
      (node (ref "JP1") (pin "2") (pinfunction "2_2") (pintype "passive"))
      (node (ref "P1") (pin "2") (pinfunction "2_2") (pintype "bidirectional"))
    )
    (net (code "55") (name "Net-(JP1-Pad10)") (class "Default")
      (node (ref "JP1") (pin "10") (pinfunction "10_10") (pintype "passive"))
      (node (ref "JP1") (pin "9") (pinfunction "9_9") (pintype "passive"))
      (node (ref "P2") (pin "2") (pinfunction "2_2") (pintype "bidirectional"))
    )
    (net (code "56") (name "Net-(Q1-PadE)") (class "Default")
      (node (ref "Q1") (pin "E") (pinfunction "E_E") (pintype "passive"))
      (node (ref "R26") (pin "2") (pinfunction "2_2") (pintype "passive"))
    )
    (net (code "57") (name "Net-(Q2-PadE)") (class "Default")
      (node (ref "Q2") (pin "E") (pinfunction "E_E") (pintype "passive"))
      (node (ref "R22") (pin "2") (pinfunction "2_2") (pintype "passive"))
    )
    (net (code "58") (name "Net-(R7-S)") (class "Default")
      (node (ref "R24") (pin "1") (pinfunction "1_1") (pintype "passive"))
      (node (ref "R7") (pin "P$2") (pinfunction "S_P$2") (pintype "passive"))
    )
    (net (code "59") (name "Net-(R18-S)") (class "Default")
      (node (ref "R18") (pin "P$2") (pinfunction "S_P$2") (pintype "passive"))
      (node (ref "R34") (pin "1") (pinfunction "1_1") (pintype "passive"))
    )
    (net (code "60") (name "Net-(R33-S)") (class "Default")
      (node (ref "R33") (pin "P$2") (pinfunction "S_P$2") (pintype "passive"))
      (node (ref "R40") (pin "2") (pinfunction "2_2") (pintype "passive"))
    )
    (net (code "61") (name "Net-(R100-A)") (class "Default")
      (node (ref "R100") (pin "2") (pinfunction "S_2") (pintype "passive"))
      (node (ref "R100") (pin "3") (pinfunction "A_3") (pintype "passive"))
      (node (ref "R36") (pin "2") (pinfunction "2_2") (pintype "passive"))
    )
    (net (code "62") (name "VCC") (class "Default")
      (node (ref "C12") (pin "+") (pinfunction "+_+") (pintype "passive"))
      (node (ref "C13") (pin "1") (pinfunction "1_1") (pintype "passive"))
      (node (ref "C20") (pin "1") (pinfunction "1_1") (pintype "passive"))
      (node (ref "C28") (pin "1") (pinfunction "1_1") (pintype "passive"))
      (node (ref "C5") (pin "1") (pinfunction "1_1") (pintype "passive"))
      (node (ref "D3") (pin "C") (pinfunction "C_C") (pintype "passive"))
      (node (ref "IC1") (pin "8") (pinfunction "V+_8") (pintype "power_in"))
      (node (ref "IC2") (pin "16") (pinfunction "V+_16") (pintype "power_in"))
      (node (ref "IC3") (pin "8") (pinfunction "V+_8") (pintype "power_in"))
      (node (ref "IC4") (pin "11") (pinfunction "V+_11") (pintype "power_in"))
      (node (ref "IC5") (pin "4") (pinfunction "V+_4") (pintype "power_in"))
      (node (ref "IC6") (pin "4") (pinfunction "V+_4") (pintype "power_in"))
      (node (ref "P1") (pin "1") (pinfunction "1_1") (pintype "bidirectional"))
      (node (ref "R47") (pin "2") (pinfunction "2_2") (pintype "passive"))
      (node (ref "R7") (pin "P$1") (pinfunction "E_P$1") (pintype "passive"))
    )
    (net (code "63") (name "VEE") (class "Default")
      (node (ref "C10") (pin "2") (pinfunction "2_2") (pintype "passive"))
      (node (ref "C14") (pin "-") (pinfunction "-_-") (pintype "passive"))
      (node (ref "C15") (pin "2") (pinfunction "2_2") (pintype "passive"))
      (node (ref "C19") (pin "2") (pinfunction "2_2") (pintype "passive"))
      (node (ref "C21") (pin "2") (pinfunction "2_2") (pintype "passive"))
      (node (ref "D4") (pin "A") (pinfunction "A_A") (pintype "passive"))
      (node (ref "IC1") (pin "4") (pinfunction "V-_4") (pintype "power_in"))
      (node (ref "IC2") (pin "9") (pinfunction "V-_9") (pintype "power_in"))
      (node (ref "IC3") (pin "4") (pinfunction "V-_4") (pintype "power_in"))
      (node (ref "IC4") (pin "6") (pinfunction "V-_6") (pintype "power_in"))
      (node (ref "IC5") (pin "11") (pinfunction "V-_11") (pintype "power_in"))
      (node (ref "IC6") (pin "11") (pinfunction "V-_11") (pintype "power_in"))
      (node (ref "P2") (pin "1") (pinfunction "1_1") (pintype "bidirectional"))
      (node (ref "R39") (pin "1") (pinfunction "1_1") (pintype "passive"))
    )
    (net (code "64") (name "unconnected-(IC2E-MODE-Pad1)") (class "Default")
      (node (ref "IC2") (pin "1") (pinfunction "MODE_1") (pintype "input"))
    )
    (net (code "65") (name "unconnected-(IC4A-B-Pad7)") (class "Default")
      (node (ref "IC4") (pin "7") (pinfunction "B_7") (pintype "passive"))
    )
    (net (code "66") (name "unconnected-(IC4A-E-Pad8)") (class "Default")
      (node (ref "IC4") (pin "8") (pinfunction "E_8") (pintype "passive"))
    )
    (net (code "67") (name "unconnected-(IC4B-B-Pad10)") (class "Default")
      (node (ref "IC4") (pin "10") (pinfunction "B_10") (pintype "passive"))
    )
    (net (code "68") (name "unconnected-(IC4B-E-Pad9)") (class "Default")
      (node (ref "IC4") (pin "9") (pinfunction "E_9") (pintype "passive"))
    )
    (net (code "69") (name "unconnected-(IC4C-I_DIODE-Pad2)") (class "Default")
      (node (ref "IC4") (pin "2") (pinfunction "I_DIODE_2") (pintype "input"))
    )
    (net (code "70") (name "unconnected-(IC4D-I_DIODE-Pad15)") (class "Default")
      (node (ref "IC4") (pin "15") (pinfunction "I_DIODE_15") (pintype "input"))
    )
    (net (code "71") (name "unconnected-(J1-2-PadP2)") (class "Default")
      (node (ref "J1") (pin "P2") (pinfunction "2_P2") (pintype "passive"))
    )
    (net (code "72") (name "unconnected-(J2-2-PadP2)") (class "Default")
      (node (ref "J2") (pin "P2") (pinfunction "2_P2") (pintype "passive"))
    )
    (net (code "73") (name "unconnected-(J3-2-PadP2)") (class "Default")
      (node (ref "J3") (pin "P2") (pinfunction "2_P2") (pintype "passive"))
    )
    (net (code "74") (name "unconnected-(J4-2-PadP2)") (class "Default")
      (node (ref "J4") (pin "P2") (pinfunction "2_P2") (pintype "passive"))
    )
    (net (code "75") (name "unconnected-(J5-2-PadP2)") (class "Default")
      (node (ref "J5") (pin "P2") (pinfunction "2_P2") (pintype "passive"))
    )
    (net (code "76") (name "unconnected-(J6-2-PadP2)") (class "Default")
      (node (ref "J6") (pin "P2") (pinfunction "2_P2") (pintype "passive"))
    )
    (net (code "77") (name "unconnected-(J8-2-PadP2)") (class "Default")
      (node (ref "J8") (pin "P2") (pinfunction "2_P2") (pintype "passive"))
    )
    (net (code "78") (name "unconnected-(J9-2-PadP2)") (class "Default")
      (node (ref "J9") (pin "P2") (pinfunction "2_P2") (pintype "passive"))
    )
  )
)
